# 75x35_2P-BOB.net
KiCad netlist of a schematic drawn in EAGLE
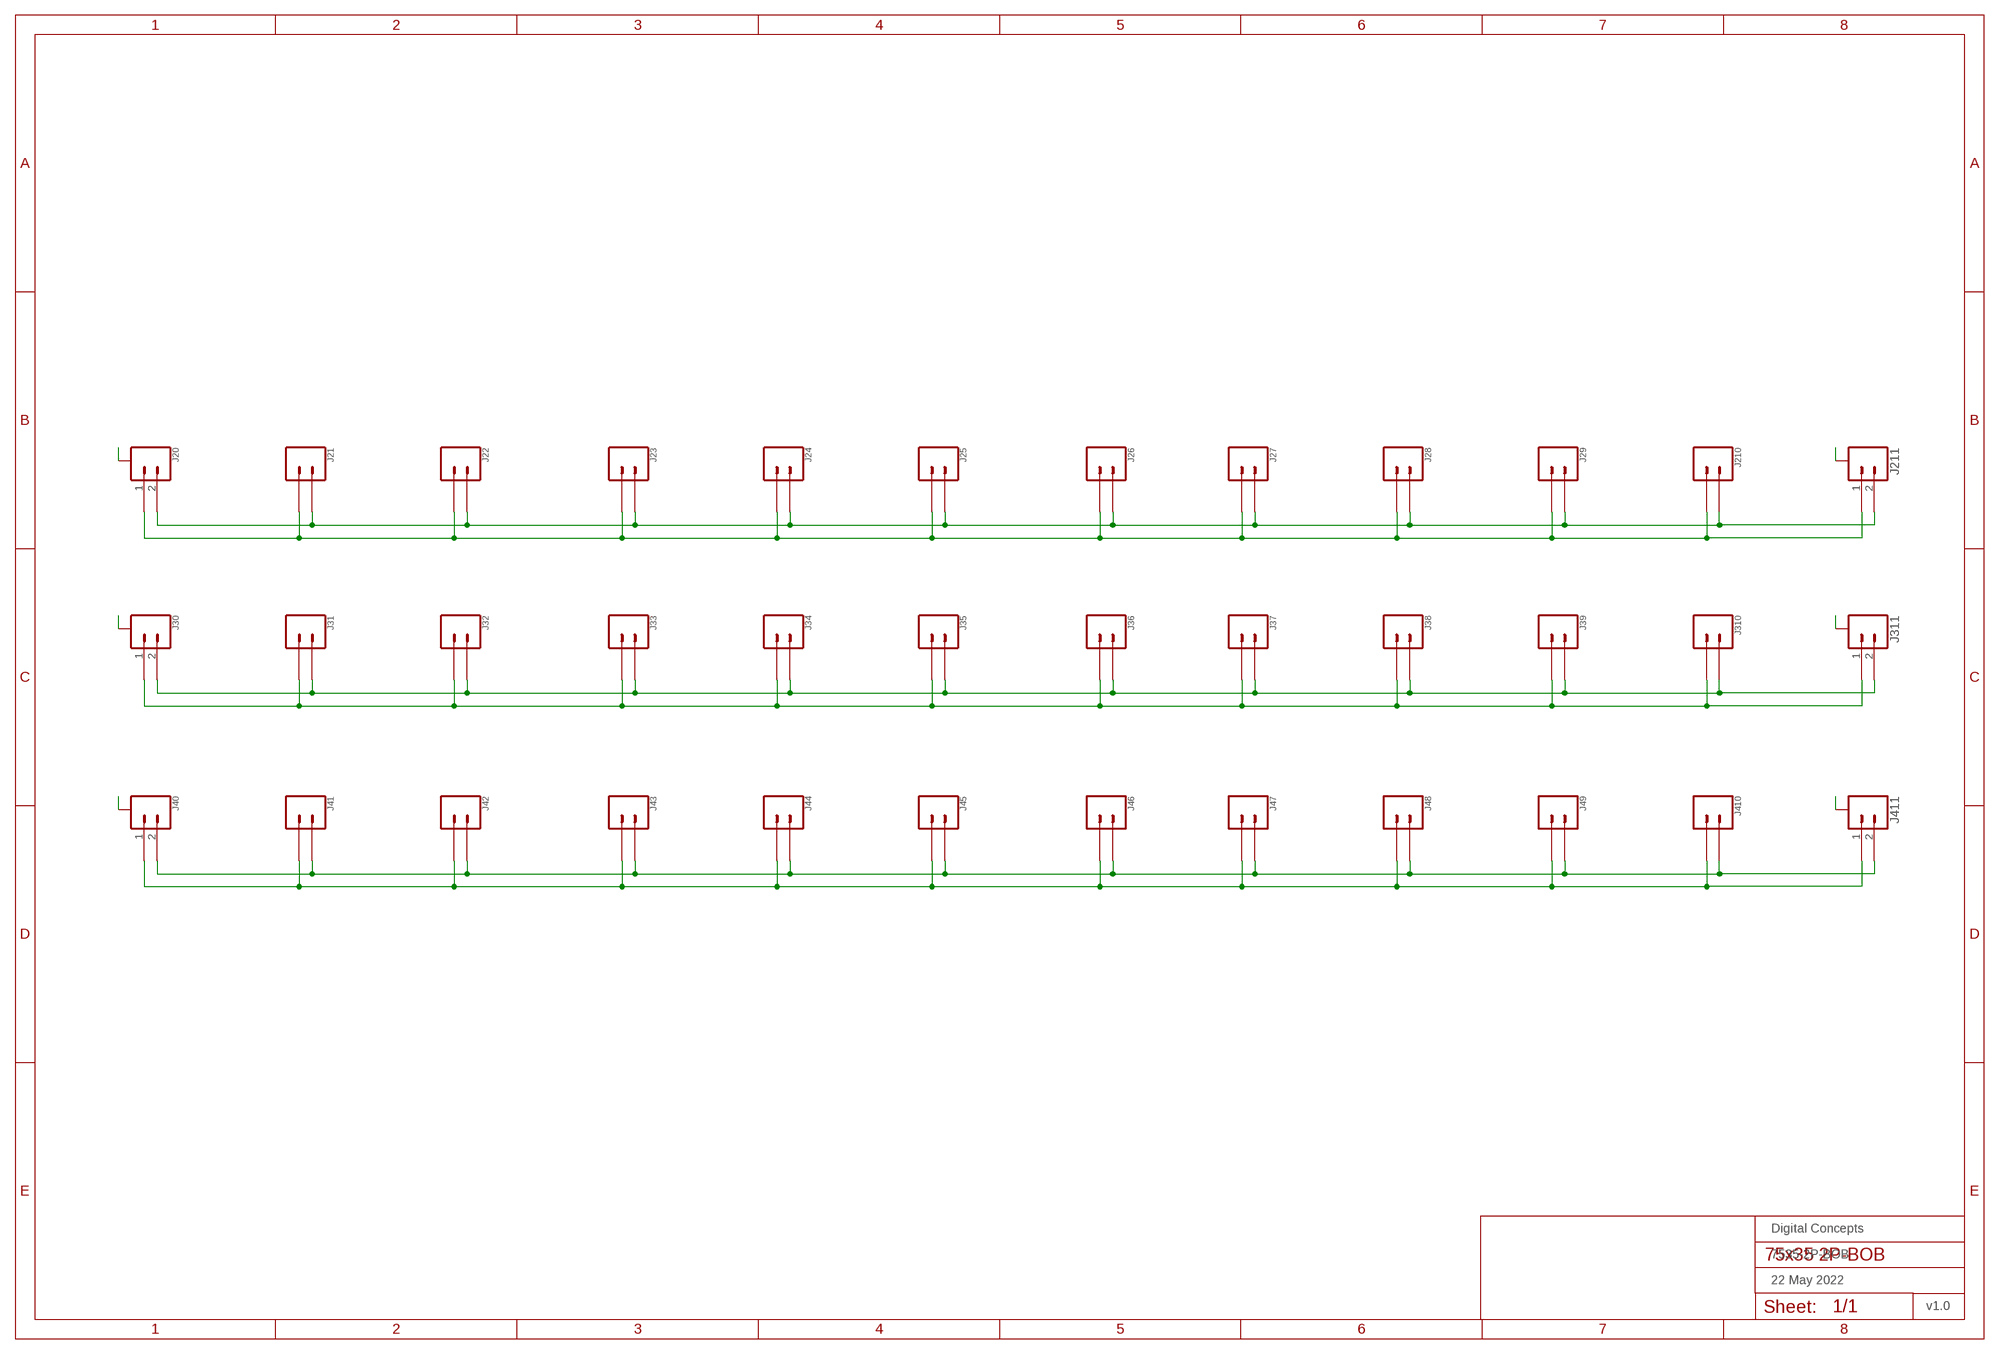
[diagram p0: schematic, sheet 1]

(export (version "E")
  (design (tool "Eeschema 10.0.6"))
  (components
    (comp (ref "J20")
      (value "JST-SH1.0-2-SMD-VERTICAL")
      (footprint "eagle-import:JST-SH1.0-2-VERTICAL")
      (libsource (lib "eagle-import") (part "JST-SH1.0-2-SMD-VERTICAL"))
    )
    (comp (ref "J21")
      (value "JST-GH1.25-2-VERTICAL")
      (footprint "eagle-import:JST-GH1.25-2-VERTICAL")
      (libsource (lib "eagle-import") (part "JST-GH1.25-2-VERTICAL"))
    )
    (comp (ref "J22")
      (value "JST-PH2.0-2-VERTICAL")
      (footprint "eagle-import:JST-PH2.0-2-VERTICAL")
      (libsource (lib "eagle-import") (part "JST-PH2.0-2-VERTICAL"))
    )
    (comp (ref "J23")
      (value "HEADER-1X2-GENERIC")
      (footprint "eagle-import:CONN_02-GENERIC")
      (libsource (lib "eagle-import") (part "HEADER-1X2-GENERIC"))
    )
    (comp (ref "J24")
      (value "HEADER-1X2-GENERIC")
      (footprint "eagle-import:CONN_02-GENERIC")
      (libsource (lib "eagle-import") (part "HEADER-1X2-GENERIC"))
    )
    (comp (ref "J25")
      (value "HEADER-1X2-GENERIC")
      (footprint "eagle-import:CONN_02-GENERIC")
      (libsource (lib "eagle-import") (part "HEADER-1X2-GENERIC"))
    )
    (comp (ref "J26")
      (value "HEADER-1X2-GENERIC")
      (footprint "eagle-import:CONN_02-GENERIC")
      (libsource (lib "eagle-import") (part "HEADER-1X2-GENERIC"))
    )
    (comp (ref "J27")
      (value "HEADER-1X2-GENERIC")
      (footprint "eagle-import:CONN_02-GENERIC")
      (libsource (lib "eagle-import") (part "HEADER-1X2-GENERIC"))
    )
    (comp (ref "J28")
      (value "HEADER-1X2-GENERIC")
      (footprint "eagle-import:CONN_02-GENERIC")
      (libsource (lib "eagle-import") (part "HEADER-1X2-GENERIC"))
    )
    (comp (ref "J29")
      (value "JST-PH2.0-2-VERTICAL")
      (footprint "eagle-import:JST-PH2.0-2-VERTICAL")
      (libsource (lib "eagle-import") (part "JST-PH2.0-2-VERTICAL"))
    )
    (comp (ref "J30")
      (value "JST-SH1.0-2-SMD-VERTICAL")
      (footprint "eagle-import:JST-SH1.0-2-VERTICAL")
      (libsource (lib "eagle-import") (part "JST-SH1.0-2-SMD-VERTICAL"))
    )
    (comp (ref "J31")
      (value "JST-GH1.25-2-VERTICAL")
      (footprint "eagle-import:JST-GH1.25-2-VERTICAL")
      (libsource (lib "eagle-import") (part "JST-GH1.25-2-VERTICAL"))
    )
    (comp (ref "J32")
      (value "JST-PH2.0-2-VERTICAL")
      (footprint "eagle-import:JST-PH2.0-2-VERTICAL")
      (libsource (lib "eagle-import") (part "JST-PH2.0-2-VERTICAL"))
    )
    (comp (ref "J33")
      (value "HEADER-1X2-GENERIC")
      (footprint "eagle-import:CONN_02-GENERIC")
      (libsource (lib "eagle-import") (part "HEADER-1X2-GENERIC"))
    )
    (comp (ref "J34")
      (value "HEADER-1X2-GENERIC")
      (footprint "eagle-import:CONN_02-GENERIC")
      (libsource (lib "eagle-import") (part "HEADER-1X2-GENERIC"))
    )
    (comp (ref "J35")
      (value "HEADER-1X2-GENERIC")
      (footprint "eagle-import:CONN_02-GENERIC")
      (libsource (lib "eagle-import") (part "HEADER-1X2-GENERIC"))
    )
    (comp (ref "J36")
      (value "HEADER-1X2-GENERIC")
      (footprint "eagle-import:CONN_02-GENERIC")
      (libsource (lib "eagle-import") (part "HEADER-1X2-GENERIC"))
    )
    (comp (ref "J37")
      (value "HEADER-1X2-GENERIC")
      (footprint "eagle-import:CONN_02-GENERIC")
      (libsource (lib "eagle-import") (part "HEADER-1X2-GENERIC"))
    )
    (comp (ref "J38")
      (value "HEADER-1X2-GENERIC")
      (footprint "eagle-import:CONN_02-GENERIC")
      (libsource (lib "eagle-import") (part "HEADER-1X2-GENERIC"))
    )
    (comp (ref "J39")
      (value "JST-PH2.0-2-VERTICAL")
      (footprint "eagle-import:JST-PH2.0-2-VERTICAL")
      (libsource (lib "eagle-import") (part "JST-PH2.0-2-VERTICAL"))
    )
    (comp (ref "J40")
      (value "JST-SH1.0-2-SMD-VERTICAL")
      (footprint "eagle-import:JST-SH1.0-2-VERTICAL")
      (libsource (lib "eagle-import") (part "JST-SH1.0-2-SMD-VERTICAL"))
    )
    (comp (ref "J41")
      (value "JST-GH1.25-2-VERTICAL")
      (footprint "eagle-import:JST-GH1.25-2-VERTICAL")
      (libsource (lib "eagle-import") (part "JST-GH1.25-2-VERTICAL"))
    )
    (comp (ref "J42")
      (value "JST-PH2.0-2-VERTICAL")
      (footprint "eagle-import:JST-PH2.0-2-VERTICAL")
      (libsource (lib "eagle-import") (part "JST-PH2.0-2-VERTICAL"))
    )
    (comp (ref "J43")
      (value "HEADER-1X2-GENERIC")
      (footprint "eagle-import:CONN_02-GENERIC")
      (libsource (lib "eagle-import") (part "HEADER-1X2-GENERIC"))
    )
    (comp (ref "J44")
      (value "HEADER-1X2-GENERIC")
      (footprint "eagle-import:CONN_02-GENERIC")
      (libsource (lib "eagle-import") (part "HEADER-1X2-GENERIC"))
    )
    (comp (ref "J45")
      (value "HEADER-1X2-GENERIC")
      (footprint "eagle-import:CONN_02-GENERIC")
      (libsource (lib "eagle-import") (part "HEADER-1X2-GENERIC"))
    )
    (comp (ref "J46")
      (value "HEADER-1X2-GENERIC")
      (footprint "eagle-import:CONN_02-GENERIC")
      (libsource (lib "eagle-import") (part "HEADER-1X2-GENERIC"))
    )
    (comp (ref "J47")
      (value "HEADER-1X2-GENERIC")
      (footprint "eagle-import:CONN_02-GENERIC")
      (libsource (lib "eagle-import") (part "HEADER-1X2-GENERIC"))
    )
    (comp (ref "J48")
      (value "HEADER-1X2-GENERIC")
      (footprint "eagle-import:CONN_02-GENERIC")
      (libsource (lib "eagle-import") (part "HEADER-1X2-GENERIC"))
    )
    (comp (ref "J49")
      (value "JST-PH2.0-2-VERTICAL")
      (footprint "eagle-import:JST-PH2.0-2-VERTICAL")
      (libsource (lib "eagle-import") (part "JST-PH2.0-2-VERTICAL"))
    )
    (comp (ref "J210")
      (value "JST-GH1.25-2-VERTICAL")
      (footprint "eagle-import:JST-GH1.25-2-VERTICAL")
      (libsource (lib "eagle-import") (part "JST-GH1.25-2-VERTICAL"))
    )
    (comp (ref "J211")
      (value "JST-SH1.0-2-SMD-VERTICAL")
      (footprint "eagle-import:JST-SH1.0-2-VERTICAL")
      (libsource (lib "eagle-import") (part "JST-SH1.0-2-SMD-VERTICAL"))
    )
    (comp (ref "J310")
      (value "JST-GH1.25-2-VERTICAL")
      (footprint "eagle-import:JST-GH1.25-2-VERTICAL")
      (libsource (lib "eagle-import") (part "JST-GH1.25-2-VERTICAL"))
    )
    (comp (ref "J311")
      (value "JST-SH1.0-2-SMD-VERTICAL")
      (footprint "eagle-import:JST-SH1.0-2-VERTICAL")
      (libsource (lib "eagle-import") (part "JST-SH1.0-2-SMD-VERTICAL"))
    )
    (comp (ref "J410")
      (value "JST-GH1.25-2-VERTICAL")
      (footprint "eagle-import:JST-GH1.25-2-VERTICAL")
      (libsource (lib "eagle-import") (part "JST-GH1.25-2-VERTICAL"))
    )
    (comp (ref "J411")
      (value "JST-SH1.0-2-SMD-VERTICAL")
      (footprint "eagle-import:JST-SH1.0-2-VERTICAL")
      (libsource (lib "eagle-import") (part "JST-SH1.0-2-SMD-VERTICAL"))
    )
  )
  (nets
    (net (code "1") (name "/A") (class "Default")
      (node (ref "J20") (pin "A@1") (pinfunction "A_A@1") (pintype "power_in"))
      (node (ref "J20") (pin "A@2") (pinfunction "A_A@2") (pintype "power_in"))
      (node (ref "J211") (pin "A@1") (pinfunction "A_A@1") (pintype "power_in"))
      (node (ref "J211") (pin "A@2") (pinfunction "A_A@2") (pintype "power_in"))
      (node (ref "J30") (pin "A@1") (pinfunction "A_A@1") (pintype "power_in"))
      (node (ref "J30") (pin "A@2") (pinfunction "A_A@2") (pintype "power_in"))
      (node (ref "J311") (pin "A@1") (pinfunction "A_A@1") (pintype "power_in"))
      (node (ref "J311") (pin "A@2") (pinfunction "A_A@2") (pintype "power_in"))
      (node (ref "J40") (pin "A@1") (pinfunction "A_A@1") (pintype "power_in"))
      (node (ref "J40") (pin "A@2") (pinfunction "A_A@2") (pintype "power_in"))
      (node (ref "J411") (pin "A@1") (pinfunction "A_A@1") (pintype "power_in"))
      (node (ref "J411") (pin "A@2") (pinfunction "A_A@2") (pintype "power_in"))
    )
    (net (code "2") (name "Net-(J20-Pad1)") (class "Default")
      (node (ref "J20") (pin "1") (pinfunction "1_1") (pintype "passive"))
      (node (ref "J21") (pin "1") (pinfunction "1_1") (pintype "passive"))
      (node (ref "J210") (pin "1") (pinfunction "1_1") (pintype "passive"))
      (node (ref "J211") (pin "1") (pinfunction "1_1") (pintype "passive"))
      (node (ref "J22") (pin "1") (pinfunction "1_1") (pintype "passive"))
      (node (ref "J23") (pin "1") (pinfunction "1_1") (pintype "passive"))
      (node (ref "J24") (pin "1") (pinfunction "1_1") (pintype "passive"))
      (node (ref "J25") (pin "1") (pinfunction "1_1") (pintype "passive"))
      (node (ref "J26") (pin "1") (pinfunction "1_1") (pintype "passive"))
      (node (ref "J27") (pin "1") (pinfunction "1_1") (pintype "passive"))
      (node (ref "J28") (pin "1") (pinfunction "1_1") (pintype "passive"))
      (node (ref "J29") (pin "1") (pinfunction "1_1") (pintype "passive"))
    )
    (net (code "3") (name "Net-(J20-Pad2)") (class "Default")
      (node (ref "J20") (pin "2") (pinfunction "2_2") (pintype "passive"))
      (node (ref "J21") (pin "2") (pinfunction "2_2") (pintype "passive"))
      (node (ref "J210") (pin "2") (pinfunction "2_2") (pintype "passive"))
      (node (ref "J211") (pin "2") (pinfunction "2_2") (pintype "passive"))
      (node (ref "J22") (pin "2") (pinfunction "2_2") (pintype "passive"))
      (node (ref "J23") (pin "2") (pinfunction "2_2") (pintype "passive"))
      (node (ref "J24") (pin "2") (pinfunction "2_2") (pintype "passive"))
      (node (ref "J25") (pin "2") (pinfunction "2_2") (pintype "passive"))
      (node (ref "J26") (pin "2") (pinfunction "2_2") (pintype "passive"))
      (node (ref "J27") (pin "2") (pinfunction "2_2") (pintype "passive"))
      (node (ref "J28") (pin "2") (pinfunction "2_2") (pintype "passive"))
      (node (ref "J29") (pin "2") (pinfunction "2_2") (pintype "passive"))
    )
    (net (code "4") (name "Net-(J30-Pad1)") (class "Default")
      (node (ref "J30") (pin "1") (pinfunction "1_1") (pintype "passive"))
      (node (ref "J31") (pin "1") (pinfunction "1_1") (pintype "passive"))
      (node (ref "J310") (pin "1") (pinfunction "1_1") (pintype "passive"))
      (node (ref "J311") (pin "1") (pinfunction "1_1") (pintype "passive"))
      (node (ref "J32") (pin "1") (pinfunction "1_1") (pintype "passive"))
      (node (ref "J33") (pin "1") (pinfunction "1_1") (pintype "passive"))
      (node (ref "J34") (pin "1") (pinfunction "1_1") (pintype "passive"))
      (node (ref "J35") (pin "1") (pinfunction "1_1") (pintype "passive"))
      (node (ref "J36") (pin "1") (pinfunction "1_1") (pintype "passive"))
      (node (ref "J37") (pin "1") (pinfunction "1_1") (pintype "passive"))
      (node (ref "J38") (pin "1") (pinfunction "1_1") (pintype "passive"))
      (node (ref "J39") (pin "1") (pinfunction "1_1") (pintype "passive"))
    )
    (net (code "5") (name "Net-(J30-Pad2)") (class "Default")
      (node (ref "J30") (pin "2") (pinfunction "2_2") (pintype "passive"))
      (node (ref "J31") (pin "2") (pinfunction "2_2") (pintype "passive"))
      (node (ref "J310") (pin "2") (pinfunction "2_2") (pintype "passive"))
      (node (ref "J311") (pin "2") (pinfunction "2_2") (pintype "passive"))
      (node (ref "J32") (pin "2") (pinfunction "2_2") (pintype "passive"))
      (node (ref "J33") (pin "2") (pinfunction "2_2") (pintype "passive"))
      (node (ref "J34") (pin "2") (pinfunction "2_2") (pintype "passive"))
      (node (ref "J35") (pin "2") (pinfunction "2_2") (pintype "passive"))
      (node (ref "J36") (pin "2") (pinfunction "2_2") (pintype "passive"))
      (node (ref "J37") (pin "2") (pinfunction "2_2") (pintype "passive"))
      (node (ref "J38") (pin "2") (pinfunction "2_2") (pintype "passive"))
      (node (ref "J39") (pin "2") (pinfunction "2_2") (pintype "passive"))
    )
    (net (code "6") (name "Net-(J40-Pad1)") (class "Default")
      (node (ref "J40") (pin "1") (pinfunction "1_1") (pintype "passive"))
      (node (ref "J41") (pin "1") (pinfunction "1_1") (pintype "passive"))
      (node (ref "J410") (pin "1") (pinfunction "1_1") (pintype "passive"))
      (node (ref "J411") (pin "1") (pinfunction "1_1") (pintype "passive"))
      (node (ref "J42") (pin "1") (pinfunction "1_1") (pintype "passive"))
      (node (ref "J43") (pin "1") (pinfunction "1_1") (pintype "passive"))
      (node (ref "J44") (pin "1") (pinfunction "1_1") (pintype "passive"))
      (node (ref "J45") (pin "1") (pinfunction "1_1") (pintype "passive"))
      (node (ref "J46") (pin "1") (pinfunction "1_1") (pintype "passive"))
      (node (ref "J47") (pin "1") (pinfunction "1_1") (pintype "passive"))
      (node (ref "J48") (pin "1") (pinfunction "1_1") (pintype "passive"))
      (node (ref "J49") (pin "1") (pinfunction "1_1") (pintype "passive"))
    )
    (net (code "7") (name "Net-(J40-Pad2)") (class "Default")
      (node (ref "J40") (pin "2") (pinfunction "2_2") (pintype "passive"))
      (node (ref "J41") (pin "2") (pinfunction "2_2") (pintype "passive"))
      (node (ref "J410") (pin "2") (pinfunction "2_2") (pintype "passive"))
      (node (ref "J411") (pin "2") (pinfunction "2_2") (pintype "passive"))
      (node (ref "J42") (pin "2") (pinfunction "2_2") (pintype "passive"))
      (node (ref "J43") (pin "2") (pinfunction "2_2") (pintype "passive"))
      (node (ref "J44") (pin "2") (pinfunction "2_2") (pintype "passive"))
      (node (ref "J45") (pin "2") (pinfunction "2_2") (pintype "passive"))
      (node (ref "J46") (pin "2") (pinfunction "2_2") (pintype "passive"))
      (node (ref "J47") (pin "2") (pinfunction "2_2") (pintype "passive"))
      (node (ref "J48") (pin "2") (pinfunction "2_2") (pintype "passive"))
      (node (ref "J49") (pin "2") (pinfunction "2_2") (pintype "passive"))
    )
  )
)
